# pcb_telemetria.net
KiCad netlist of a schematic drawn in EAGLE
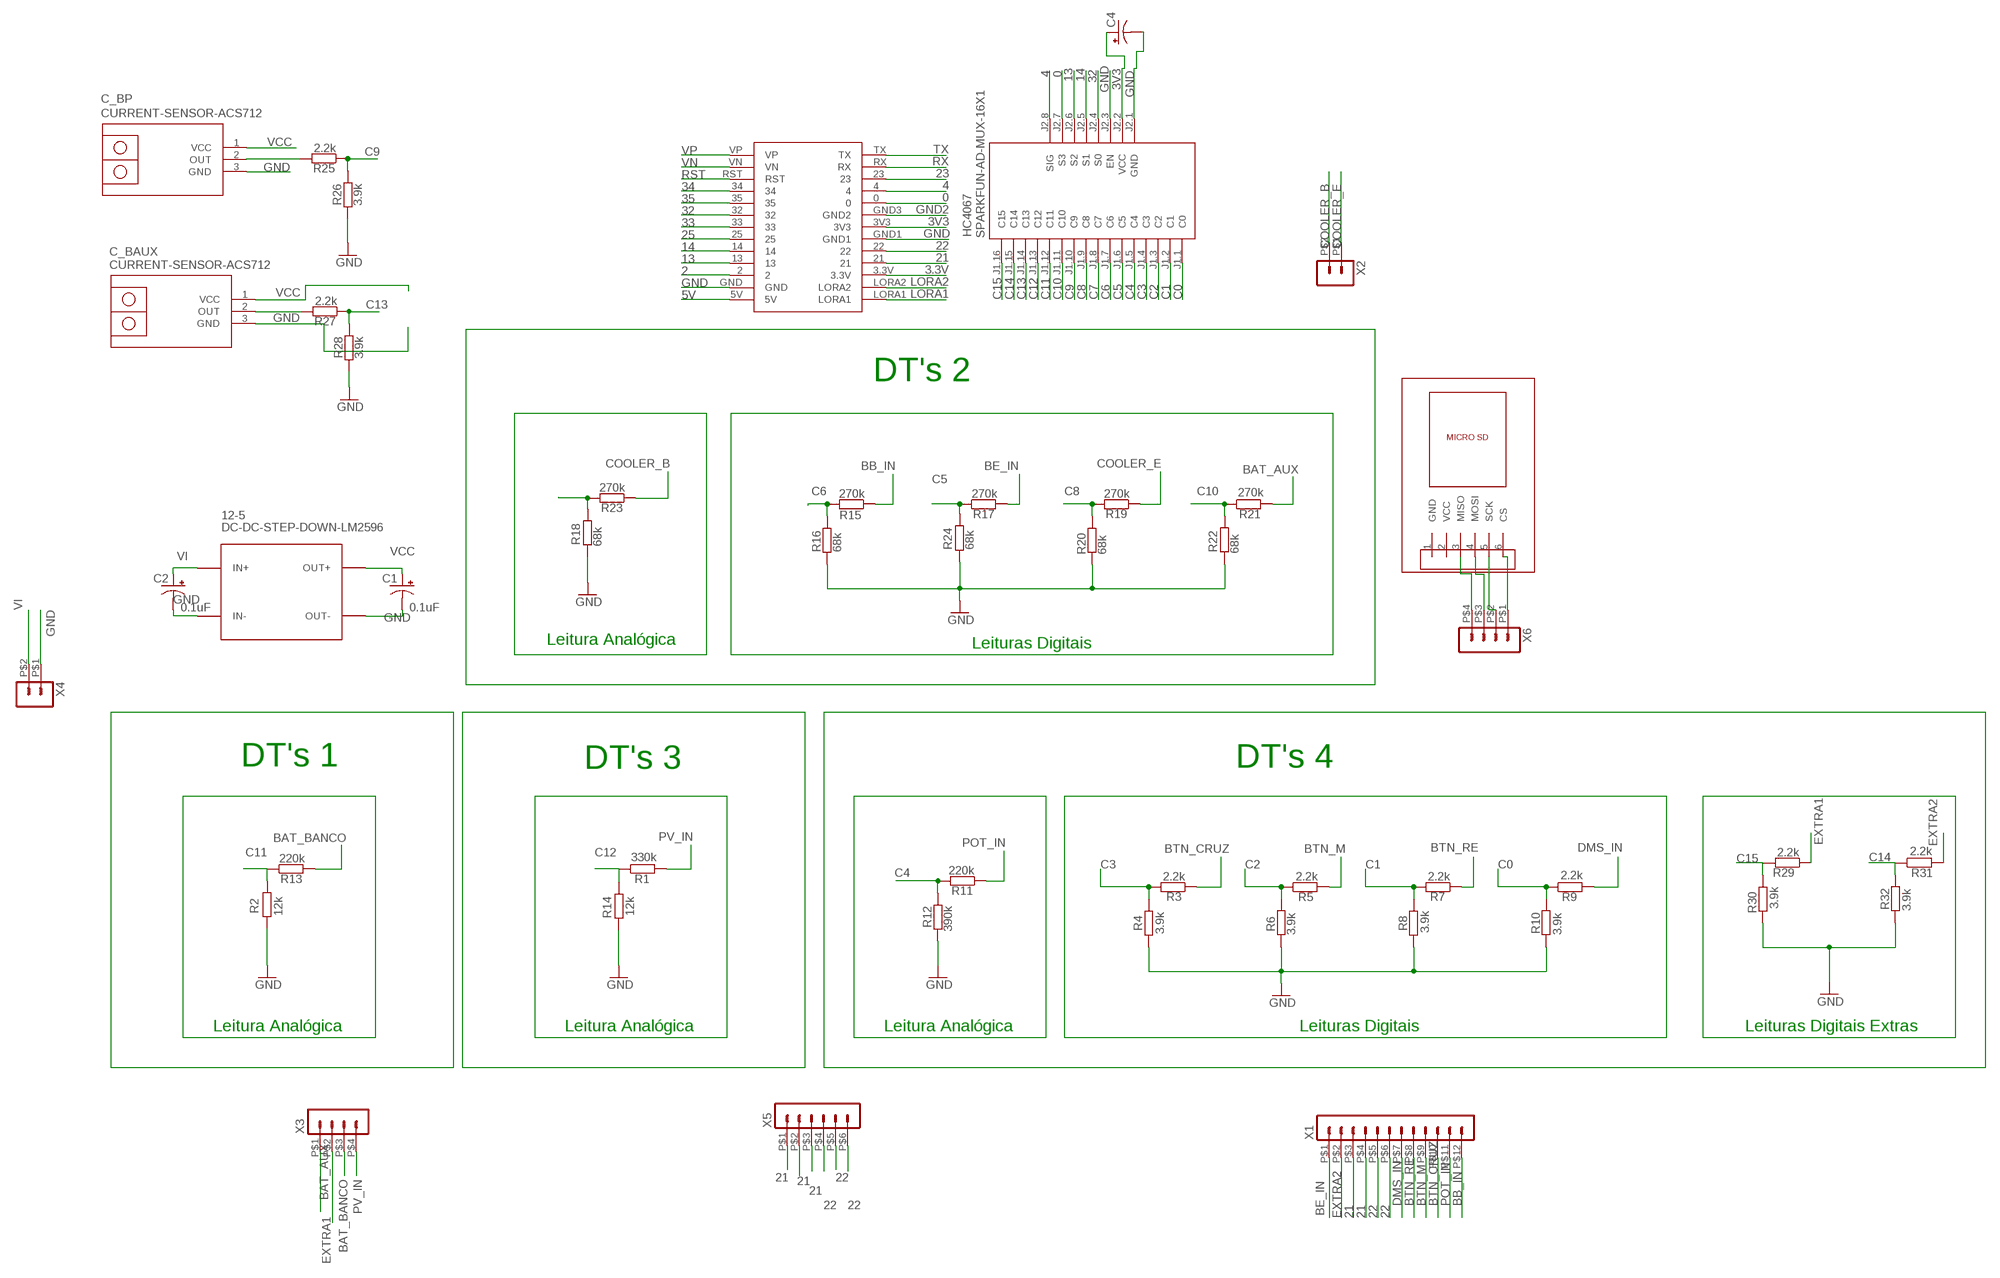
[diagram p0: schematic, sheet 1]

(export (version "E")
  (design (tool "Eeschema 10.0.6"))
  (components
    (comp (ref "12-5")
      (value "DC-DC-STEP-DOWN-LM2596")
      (footprint "eagle-import:DC-DC-STEP-DOWN-LM2596")
      (libsource (lib "eagle-import") (part "DC-DC-STEP-DOWN-LM2596"))
    )
    (comp (ref "C1")
      (value "0.1uF")
      (footprint "eagle-import:E5-5")
      (libsource (lib "eagle-import") (part "CPOL-USE5-5"))
    )
    (comp (ref "C2")
      (value "0.1uF")
      (footprint "eagle-import:E5-5")
      (libsource (lib "eagle-import") (part "CPOL-USE5-5"))
    )
    (comp (ref "C4")
      (value "CPOL-USE5-5")
      (footprint "eagle-import:E5-5")
      (libsource (lib "eagle-import") (part "CPOL-USE5-5"))
    )
    (comp (ref "C_BAUX")
      (value "CURRENT-SENSOR-ACS712")
      (footprint "eagle-import:CURRENT-SENSOR-ACS712")
      (libsource (lib "eagle-import") (part "CURRENT-SENSOR-ACS712"))
    )
    (comp (ref "C_BP")
      (value "CURRENT-SENSOR-ACS712")
      (footprint "eagle-import:CURRENT-SENSOR-ACS712")
      (libsource (lib "eagle-import") (part "CURRENT-SENSOR-ACS712"))
    )
    (comp (ref "HC4067")
      (value "SPARKFUN-AD-MUX-16X1")
      (footprint "eagle-import:SPARKFUN-AD-MUX-16X1")
      (libsource (lib "eagle-import") (part "SPARKFUN-AD-MUX-16X1"))
    )
    (comp (ref "R1")
      (value "330k")
      (footprint "eagle-import:0204_7")
      (libsource (lib "eagle-import") (part "R-EU_0204/7"))
    )
    (comp (ref "R2")
      (value "12k")
      (footprint "eagle-import:0204_7")
      (libsource (lib "eagle-import") (part "R-EU_0204/7"))
    )
    (comp (ref "R3")
      (value "2.2k")
      (footprint "eagle-import:0204_7")
      (libsource (lib "eagle-import") (part "R-EU_0204/7"))
    )
    (comp (ref "R4")
      (value "3.9k")
      (footprint "eagle-import:0204_7")
      (libsource (lib "eagle-import") (part "R-EU_0204/7"))
    )
    (comp (ref "R5")
      (value "2.2k")
      (footprint "eagle-import:0204_7")
      (libsource (lib "eagle-import") (part "R-EU_0204/7"))
    )
    (comp (ref "R6")
      (value "3.9k")
      (footprint "eagle-import:0204_7")
      (libsource (lib "eagle-import") (part "R-EU_0204/7"))
    )
    (comp (ref "R7")
      (value "2.2k")
      (footprint "eagle-import:0204_7")
      (libsource (lib "eagle-import") (part "R-EU_0204/7"))
    )
    (comp (ref "R8")
      (value "3.9k")
      (footprint "eagle-import:0204_7")
      (libsource (lib "eagle-import") (part "R-EU_0204/7"))
    )
    (comp (ref "R9")
      (value "2.2k")
      (footprint "eagle-import:0204_7")
      (libsource (lib "eagle-import") (part "R-EU_0204/7"))
    )
    (comp (ref "R10")
      (value "3.9k")
      (footprint "eagle-import:0204_7")
      (libsource (lib "eagle-import") (part "R-EU_0204/7"))
    )
    (comp (ref "R11")
      (value "220k")
      (footprint "eagle-import:0204_7")
      (libsource (lib "eagle-import") (part "R-EU_0204/7"))
    )
    (comp (ref "R12")
      (value "390k")
      (footprint "eagle-import:0204_7")
      (libsource (lib "eagle-import") (part "R-EU_0204/7"))
    )
    (comp (ref "R13")
      (value "220k")
      (footprint "eagle-import:0204_7")
      (libsource (lib "eagle-import") (part "R-EU_0204/7"))
    )
    (comp (ref "R14")
      (value "12k")
      (footprint "eagle-import:0204_7")
      (libsource (lib "eagle-import") (part "R-EU_0204/7"))
    )
    (comp (ref "R15")
      (value "270k")
      (footprint "eagle-import:0204_7")
      (libsource (lib "eagle-import") (part "R-EU_0204/7"))
    )
    (comp (ref "R16")
      (value "68k")
      (footprint "eagle-import:0204_7")
      (libsource (lib "eagle-import") (part "R-EU_0204/7"))
    )
    (comp (ref "R17")
      (value "270k")
      (footprint "eagle-import:0204_7")
      (libsource (lib "eagle-import") (part "R-EU_0204/7"))
    )
    (comp (ref "R18")
      (value "68k")
      (footprint "eagle-import:0204_7")
      (libsource (lib "eagle-import") (part "R-EU_0204/7"))
    )
    (comp (ref "R19")
      (value "270k")
      (footprint "eagle-import:0204_7")
      (libsource (lib "eagle-import") (part "R-EU_0204/7"))
    )
    (comp (ref "R20")
      (value "68k")
      (footprint "eagle-import:0204_7")
      (libsource (lib "eagle-import") (part "R-EU_0204/7"))
    )
    (comp (ref "R21")
      (value "270k")
      (footprint "eagle-import:0204_7")
      (libsource (lib "eagle-import") (part "R-EU_0204/7"))
    )
    (comp (ref "R22")
      (value "68k")
      (footprint "eagle-import:0204_7")
      (libsource (lib "eagle-import") (part "R-EU_0204/7"))
    )
    (comp (ref "R23")
      (value "270k")
      (footprint "eagle-import:0204_7")
      (libsource (lib "eagle-import") (part "R-EU_0204/7"))
    )
    (comp (ref "R24")
      (value "68k")
      (footprint "eagle-import:0204_7")
      (libsource (lib "eagle-import") (part "R-EU_0204/7"))
    )
    (comp (ref "R25")
      (value "2.2k")
      (footprint "eagle-import:0204_7")
      (libsource (lib "eagle-import") (part "R-EU_0204/7"))
    )
    (comp (ref "R26")
      (value "3.9k")
      (footprint "eagle-import:0204_7")
      (libsource (lib "eagle-import") (part "R-EU_0204/7"))
    )
    (comp (ref "R27")
      (value "2.2k")
      (footprint "eagle-import:0204_7")
      (libsource (lib "eagle-import") (part "R-EU_0204/7"))
    )
    (comp (ref "R28")
      (value "3.9k")
      (footprint "eagle-import:0204_7")
      (libsource (lib "eagle-import") (part "R-EU_0204/7"))
    )
    (comp (ref "R29")
      (value "2.2k")
      (footprint "eagle-import:0204_7")
      (libsource (lib "eagle-import") (part "R-EU_0204/7"))
    )
    (comp (ref "R30")
      (value "3.9k")
      (footprint "eagle-import:0204_7")
      (libsource (lib "eagle-import") (part "R-EU_0204/7"))
    )
    (comp (ref "R31")
      (value "2.2k")
      (footprint "eagle-import:0204_7")
      (libsource (lib "eagle-import") (part "R-EU_0204/7"))
    )
    (comp (ref "R32")
      (value "3.9k")
      (footprint "eagle-import:0204_7")
      (libsource (lib "eagle-import") (part "R-EU_0204/7"))
    )
    (comp (ref "U$1")
      (value "TTGOBEAM")
      (footprint "eagle-import:TTGOBEAM")
      (libsource (lib "eagle-import") (part "TTGOBEAM"))
    )
    (comp (ref "U$2")
      (value "MICRO_SD_MODULE")
      (footprint "eagle-import:MICRO_SD")
      (libsource (lib "eagle-import") (part "MICRO_SD_MODULE"))
    )
    (comp (ref "X1")
      (value "HEADER_POS12_43045-1212")
      (footprint "eagle-import:43045-1212")
      (libsource (lib "eagle-import") (part "HEADER_POS12_?43045-1212"))
    )
    (comp (ref "X2")
      (value "HEADER_POS2_43045-0212")
      (footprint "eagle-import:43045-0212")
      (libsource (lib "eagle-import") (part "HEADER_POS2_?43045-0212"))
    )
    (comp (ref "X3")
      (value "HEADER_POS4_43045-0412")
      (footprint "eagle-import:43045-0412")
      (libsource (lib "eagle-import") (part "HEADER_POS4_?43045-0412"))
    )
    (comp (ref "X4")
      (value "HEADER_POS2_43045-0212")
      (footprint "eagle-import:43045-0212")
      (libsource (lib "eagle-import") (part "HEADER_POS2_?43045-0212"))
    )
    (comp (ref "X5")
      (value "HEADER_POS6_43045-0612")
      (footprint "eagle-import:43045-0612")
      (libsource (lib "eagle-import") (part "HEADER_POS6_?43045-0612"))
    )
    (comp (ref "X6")
      (value "HEADER_POS4_43045-0412")
      (footprint "eagle-import:43045-0412")
      (libsource (lib "eagle-import") (part "HEADER_POS4_?43045-0412"))
    )
  )
  (nets
    (net (code "1") (name "/0") (class "Default")
      (node (ref "HC4067") (pin "J2.7") (pinfunction "S3_J2.7") (pintype "bidirectional"))
      (node (ref "U$1") (pin "0") (pinfunction "0_0") (pintype "bidirectional"))
    )
    (net (code "2") (name "/2") (class "Default")
      (node (ref "U$1") (pin "2") (pinfunction "2_2") (pintype "bidirectional"))
    )
    (net (code "3") (name "/3.3V") (class "Default")
      (node (ref "U$1") (pin "3.3V") (pinfunction "3.3V_3.3V") (pintype "bidirectional"))
    )
    (net (code "4") (name "/3V3") (class "Default")
      (node (ref "C4") (pin "+") (pinfunction "+_+") (pintype "passive"))
      (node (ref "HC4067") (pin "J2.2") (pinfunction "VCC_J2.2") (pintype "power_in"))
      (node (ref "U$1") (pin "3V3") (pinfunction "3V3_3V3") (pintype "bidirectional"))
    )
    (net (code "5") (name "/4") (class "Default")
      (node (ref "HC4067") (pin "J2.8") (pinfunction "SIG_J2.8") (pintype "bidirectional"))
      (node (ref "U$1") (pin "4") (pinfunction "4_4") (pintype "bidirectional"))
    )
    (net (code "6") (name "/5V") (class "Default")
      (node (ref "U$1") (pin "5V") (pinfunction "5V_5V") (pintype "bidirectional"))
    )
    (net (code "7") (name "/13") (class "Default")
      (node (ref "HC4067") (pin "J2.6") (pinfunction "S2_J2.6") (pintype "bidirectional"))
      (node (ref "U$1") (pin "13") (pinfunction "13_13") (pintype "bidirectional"))
    )
    (net (code "8") (name "/14") (class "Default")
      (node (ref "HC4067") (pin "J2.5") (pinfunction "S1_J2.5") (pintype "bidirectional"))
      (node (ref "U$1") (pin "14") (pinfunction "14_14") (pintype "bidirectional"))
    )
    (net (code "9") (name "/21") (class "Default")
      (node (ref "U$1") (pin "21") (pinfunction "21_21") (pintype "bidirectional"))
      (node (ref "X1") (pin "P$3") (pinfunction "3_P$3") (pintype "passive"))
      (node (ref "X1") (pin "P$4") (pinfunction "4_P$4") (pintype "passive"))
      (node (ref "X5") (pin "P$1") (pinfunction "1_P$1") (pintype "passive"))
      (node (ref "X5") (pin "P$2") (pinfunction "2_P$2") (pintype "passive"))
      (node (ref "X5") (pin "P$3") (pinfunction "3_P$3") (pintype "passive"))
    )
    (net (code "10") (name "/22") (class "Default")
      (node (ref "U$1") (pin "22") (pinfunction "22_22") (pintype "bidirectional"))
      (node (ref "X1") (pin "P$5") (pinfunction "5_P$5") (pintype "passive"))
      (node (ref "X1") (pin "P$6") (pinfunction "6_P$6") (pintype "passive"))
      (node (ref "X5") (pin "P$4") (pinfunction "4_P$4") (pintype "passive"))
      (node (ref "X5") (pin "P$5") (pinfunction "5_P$5") (pintype "passive"))
      (node (ref "X5") (pin "P$6") (pinfunction "6_P$6") (pintype "passive"))
    )
    (net (code "11") (name "/23") (class "Default")
      (node (ref "U$1") (pin "23") (pinfunction "23_23") (pintype "bidirectional"))
    )
    (net (code "12") (name "/25") (class "Default")
      (node (ref "U$1") (pin "25") (pinfunction "25_25") (pintype "bidirectional"))
    )
    (net (code "13") (name "/32") (class "Default")
      (node (ref "HC4067") (pin "J2.4") (pinfunction "S0_J2.4") (pintype "bidirectional"))
      (node (ref "U$1") (pin "32") (pinfunction "32_32") (pintype "bidirectional"))
    )
    (net (code "14") (name "/33") (class "Default")
      (node (ref "U$1") (pin "33") (pinfunction "33_33") (pintype "bidirectional"))
    )
    (net (code "15") (name "/34") (class "Default")
      (node (ref "U$1") (pin "34") (pinfunction "34_34") (pintype "bidirectional"))
    )
    (net (code "16") (name "/35") (class "Default")
      (node (ref "U$1") (pin "35") (pinfunction "35_35") (pintype "bidirectional"))
    )
    (net (code "17") (name "/BAT_AUX") (class "Default")
      (node (ref "R21") (pin "2") (pinfunction "2_2") (pintype "passive"))
      (node (ref "X3") (pin "P$1") (pinfunction "1_P$1") (pintype "passive"))
    )
    (net (code "18") (name "/BAT_BANCO") (class "Default")
      (node (ref "R13") (pin "2") (pinfunction "2_2") (pintype "passive"))
      (node (ref "X3") (pin "P$3") (pinfunction "3_P$3") (pintype "passive"))
    )
    (net (code "19") (name "/BB_IN") (class "Default")
      (node (ref "R15") (pin "1") (pinfunction "1_1") (pintype "passive"))
      (node (ref "X1") (pin "P$12") (pinfunction "12_P$12") (pintype "passive"))
    )
    (net (code "20") (name "/BE_IN") (class "Default")
      (node (ref "R17") (pin "2") (pinfunction "2_2") (pintype "passive"))
      (node (ref "X1") (pin "P$1") (pinfunction "1_P$1") (pintype "passive"))
    )
    (net (code "21") (name "/BTN_CRUZ") (class "Default")
      (node (ref "R3") (pin "1") (pinfunction "1_1") (pintype "passive"))
      (node (ref "X1") (pin "P$10") (pinfunction "10_P$10") (pintype "passive"))
    )
    (net (code "22") (name "/BTN_M") (class "Default")
      (node (ref "R5") (pin "2") (pinfunction "2_2") (pintype "passive"))
      (node (ref "X1") (pin "P$9") (pinfunction "9_P$9") (pintype "passive"))
    )
    (net (code "23") (name "/BTN_RE") (class "Default")
      (node (ref "R7") (pin "1") (pinfunction "1_1") (pintype "passive"))
      (node (ref "X1") (pin "P$8") (pinfunction "8_P$8") (pintype "passive"))
    )
    (net (code "24") (name "/C0") (class "Default")
      (node (ref "HC4067") (pin "J1.1") (pinfunction "C0_J1.1") (pintype "bidirectional"))
      (node (ref "R10") (pin "2") (pinfunction "2_2") (pintype "passive"))
      (node (ref "R9") (pin "1") (pinfunction "1_1") (pintype "passive"))
    )
    (net (code "25") (name "/C1") (class "Default")
      (node (ref "HC4067") (pin "J1.2") (pinfunction "C1_J1.2") (pintype "bidirectional"))
      (node (ref "R7") (pin "2") (pinfunction "2_2") (pintype "passive"))
      (node (ref "R8") (pin "1") (pinfunction "1_1") (pintype "passive"))
    )
    (net (code "26") (name "/C2") (class "Default")
      (node (ref "HC4067") (pin "J1.3") (pinfunction "C2_J1.3") (pintype "bidirectional"))
      (node (ref "R5") (pin "1") (pinfunction "1_1") (pintype "passive"))
      (node (ref "R6") (pin "2") (pinfunction "2_2") (pintype "passive"))
    )
    (net (code "27") (name "/C3") (class "Default")
      (node (ref "HC4067") (pin "J1.4") (pinfunction "C3_J1.4") (pintype "bidirectional"))
      (node (ref "R3") (pin "2") (pinfunction "2_2") (pintype "passive"))
      (node (ref "R4") (pin "1") (pinfunction "1_1") (pintype "passive"))
    )
    (net (code "28") (name "/C4") (class "Default")
      (node (ref "HC4067") (pin "J1.5") (pinfunction "C4_J1.5") (pintype "bidirectional"))
      (node (ref "R11") (pin "2") (pinfunction "2_2") (pintype "passive"))
      (node (ref "R12") (pin "1") (pinfunction "1_1") (pintype "passive"))
    )
    (net (code "29") (name "/C5") (class "Default")
      (node (ref "HC4067") (pin "J1.6") (pinfunction "C5_J1.6") (pintype "bidirectional"))
      (node (ref "R17") (pin "1") (pinfunction "1_1") (pintype "passive"))
      (node (ref "R24") (pin "1") (pinfunction "1_1") (pintype "passive"))
    )
    (net (code "30") (name "/C6") (class "Default")
      (node (ref "HC4067") (pin "J1.7") (pinfunction "C6_J1.7") (pintype "bidirectional"))
      (node (ref "R15") (pin "2") (pinfunction "2_2") (pintype "passive"))
      (node (ref "R16") (pin "1") (pinfunction "1_1") (pintype "passive"))
    )
    (net (code "31") (name "/C7") (class "Default")
      (node (ref "HC4067") (pin "J1.8") (pinfunction "C7_J1.8") (pintype "bidirectional"))
      (node (ref "R18") (pin "2") (pinfunction "2_2") (pintype "passive"))
      (node (ref "R23") (pin "2") (pinfunction "2_2") (pintype "passive"))
    )
    (net (code "32") (name "/C8") (class "Default")
      (node (ref "HC4067") (pin "J1.9") (pinfunction "C8_J1.9") (pintype "bidirectional"))
      (node (ref "R19") (pin "2") (pinfunction "2_2") (pintype "passive"))
      (node (ref "R20") (pin "1") (pinfunction "1_1") (pintype "passive"))
    )
    (net (code "33") (name "/C9") (class "Default")
      (node (ref "HC4067") (pin "J1.10") (pinfunction "C9_J1.10") (pintype "bidirectional"))
      (node (ref "R25") (pin "1") (pinfunction "1_1") (pintype "passive"))
      (node (ref "R26") (pin "1") (pinfunction "1_1") (pintype "passive"))
    )
    (net (code "34") (name "/C10") (class "Default")
      (node (ref "HC4067") (pin "J1.11") (pinfunction "C10_J1.11") (pintype "bidirectional"))
      (node (ref "R21") (pin "1") (pinfunction "1_1") (pintype "passive"))
      (node (ref "R22") (pin "2") (pinfunction "2_2") (pintype "passive"))
    )
    (net (code "35") (name "/C11") (class "Default")
      (node (ref "HC4067") (pin "J1.12") (pinfunction "C11_J1.12") (pintype "bidirectional"))
      (node (ref "R13") (pin "1") (pinfunction "1_1") (pintype "passive"))
      (node (ref "R2") (pin "2") (pinfunction "2_2") (pintype "passive"))
    )
    (net (code "36") (name "/C12") (class "Default")
      (node (ref "HC4067") (pin "J1.13") (pinfunction "C12_J1.13") (pintype "bidirectional"))
      (node (ref "R1") (pin "1") (pinfunction "1_1") (pintype "passive"))
      (node (ref "R14") (pin "2") (pinfunction "2_2") (pintype "passive"))
    )
    (net (code "37") (name "/C13") (class "Default")
      (node (ref "HC4067") (pin "J1.14") (pinfunction "C13_J1.14") (pintype "bidirectional"))
      (node (ref "R27") (pin "1") (pinfunction "1_1") (pintype "passive"))
      (node (ref "R28") (pin "1") (pinfunction "1_1") (pintype "passive"))
    )
    (net (code "38") (name "/C14") (class "Default")
      (node (ref "HC4067") (pin "J1.15") (pinfunction "C14_J1.15") (pintype "bidirectional"))
      (node (ref "R31") (pin "1") (pinfunction "1_1") (pintype "passive"))
      (node (ref "R32") (pin "2") (pinfunction "2_2") (pintype "passive"))
    )
    (net (code "39") (name "/C15") (class "Default")
      (node (ref "HC4067") (pin "J1.16") (pinfunction "C15_J1.16") (pintype "bidirectional"))
      (node (ref "R29") (pin "2") (pinfunction "2_2") (pintype "passive"))
      (node (ref "R30") (pin "1") (pinfunction "1_1") (pintype "passive"))
    )
    (net (code "40") (name "/COOLER_B") (class "Default")
      (node (ref "R23") (pin "1") (pinfunction "1_1") (pintype "passive"))
      (node (ref "X2") (pin "P$2") (pinfunction "2_P$2") (pintype "passive"))
    )
    (net (code "41") (name "/COOLER_E") (class "Default")
      (node (ref "R19") (pin "1") (pinfunction "1_1") (pintype "passive"))
      (node (ref "X2") (pin "P$1") (pinfunction "1_P$1") (pintype "passive"))
    )
    (net (code "42") (name "/DMS_IN") (class "Default")
      (node (ref "R9") (pin "2") (pinfunction "2_2") (pintype "passive"))
      (node (ref "X1") (pin "P$7") (pinfunction "7_P$7") (pintype "passive"))
    )
    (net (code "43") (name "/EXTRA1") (class "Default")
      (node (ref "R29") (pin "1") (pinfunction "1_1") (pintype "passive"))
      (node (ref "X3") (pin "P$2") (pinfunction "2_P$2") (pintype "passive"))
    )
    (net (code "44") (name "/EXTRA2") (class "Default")
      (node (ref "R31") (pin "2") (pinfunction "2_2") (pintype "passive"))
      (node (ref "X1") (pin "P$2") (pinfunction "2_P$2") (pintype "passive"))
    )
    (net (code "45") (name "/GND2") (class "Default")
      (node (ref "U$1") (pin "GND3") (pinfunction "GND2_GND3") (pintype "bidirectional"))
    )
    (net (code "46") (name "/LORA1") (class "Default")
      (node (ref "U$1") (pin "LORA1") (pinfunction "LORA1_LORA1") (pintype "bidirectional"))
    )
    (net (code "47") (name "/LORA2") (class "Default")
      (node (ref "U$1") (pin "LORA2") (pinfunction "LORA2_LORA2") (pintype "bidirectional"))
    )
    (net (code "48") (name "/POT_IN") (class "Default")
      (node (ref "R11") (pin "1") (pinfunction "1_1") (pintype "passive"))
      (node (ref "X1") (pin "P$11") (pinfunction "11_P$11") (pintype "passive"))
    )
    (net (code "49") (name "/PV_IN") (class "Default")
      (node (ref "R1") (pin "2") (pinfunction "2_2") (pintype "passive"))
      (node (ref "X3") (pin "P$4") (pinfunction "4_P$4") (pintype "passive"))
    )
    (net (code "50") (name "/RST") (class "Default")
      (node (ref "U$1") (pin "RST") (pinfunction "RST_RST") (pintype "bidirectional"))
    )
    (net (code "51") (name "/RX") (class "Default")
      (node (ref "U$1") (pin "RX") (pinfunction "RX_RX") (pintype "bidirectional"))
    )
    (net (code "52") (name "/TX") (class "Default")
      (node (ref "U$1") (pin "TX") (pinfunction "TX_TX") (pintype "bidirectional"))
    )
    (net (code "53") (name "/VCC") (class "Default")
      (node (ref "12-5") (pin "OUT+") (pinfunction "OUT+_OUT+") (pintype "bidirectional"))
      (node (ref "C1") (pin "+") (pinfunction "+_+") (pintype "passive"))
      (node (ref "C_BAUX") (pin "1") (pinfunction "VCC_1") (pintype "power_in"))
      (node (ref "C_BP") (pin "1") (pinfunction "VCC_1") (pintype "power_in"))
    )
    (net (code "54") (name "/VI") (class "Default")
      (node (ref "12-5") (pin "IN+") (pinfunction "IN+_IN+") (pintype "bidirectional"))
      (node (ref "C2") (pin "+") (pinfunction "+_+") (pintype "passive"))
      (node (ref "X4") (pin "P$2") (pinfunction "2_P$2") (pintype "passive"))
    )
    (net (code "55") (name "/VN") (class "Default")
      (node (ref "U$1") (pin "VN") (pinfunction "VN_VN") (pintype "bidirectional"))
    )
    (net (code "56") (name "/VP") (class "Default")
      (node (ref "U$1") (pin "VP") (pinfunction "VP_VP") (pintype "bidirectional"))
    )
    (net (code "57") (name "GND") (class "Default")
      (node (ref "12-5") (pin "IN-") (pinfunction "IN-_IN-") (pintype "bidirectional"))
      (node (ref "12-5") (pin "OUT-") (pinfunction "OUT-_OUT-") (pintype "bidirectional"))
      (node (ref "C1") (pin "-") (pinfunction "-_-") (pintype "passive"))
      (node (ref "C2") (pin "-") (pinfunction "-_-") (pintype "passive"))
      (node (ref "C4") (pin "-") (pinfunction "-_-") (pintype "passive"))
      (node (ref "C_BAUX") (pin "3") (pinfunction "GND_3") (pintype "power_in"))
      (node (ref "C_BP") (pin "3") (pinfunction "GND_3") (pintype "power_in"))
      (node (ref "HC4067") (pin "J2.1") (pinfunction "GND_J2.1") (pintype "power_in"))
      (node (ref "HC4067") (pin "J2.3") (pinfunction "EN_J2.3") (pintype "input"))
      (node (ref "R10") (pin "1") (pinfunction "1_1") (pintype "passive"))
      (node (ref "R12") (pin "2") (pinfunction "2_2") (pintype "passive"))
      (node (ref "R14") (pin "1") (pinfunction "1_1") (pintype "passive"))
      (node (ref "R16") (pin "2") (pinfunction "2_2") (pintype "passive"))
      (node (ref "R18") (pin "1") (pinfunction "1_1") (pintype "passive"))
      (node (ref "R2") (pin "1") (pinfunction "1_1") (pintype "passive"))
      (node (ref "R20") (pin "2") (pinfunction "2_2") (pintype "passive"))
      (node (ref "R22") (pin "1") (pinfunction "1_1") (pintype "passive"))
      (node (ref "R26") (pin "2") (pinfunction "2_2") (pintype "passive"))
      (node (ref "R28") (pin "2") (pinfunction "2_2") (pintype "passive"))
      (node (ref "R30") (pin "2") (pinfunction "2_2") (pintype "passive"))
      (node (ref "R32") (pin "1") (pinfunction "1_1") (pintype "passive"))
      (node (ref "R4") (pin "2") (pinfunction "2_2") (pintype "passive"))
      (node (ref "R6") (pin "1") (pinfunction "1_1") (pintype "passive"))
      (node (ref "R8") (pin "2") (pinfunction "2_2") (pintype "passive"))
      (node (ref "U$1") (pin "GND") (pinfunction "GND_GND") (pintype "bidirectional"))
      (node (ref "U$1") (pin "GND1") (pinfunction "GND1_GND1") (pintype "bidirectional"))
      (node (ref "X4") (pin "P$1") (pinfunction "1_P$1") (pintype "passive"))
    )
    (net (code "58") (name "Net-(C_BAUX-OUT)") (class "Default")
      (node (ref "C_BAUX") (pin "2") (pinfunction "OUT_2") (pintype "output"))
      (node (ref "R27") (pin "2") (pinfunction "2_2") (pintype "passive"))
    )
    (net (code "59") (name "Net-(C_BP-OUT)") (class "Default")
      (node (ref "C_BP") (pin "2") (pinfunction "OUT_2") (pintype "output"))
      (node (ref "R25") (pin "2") (pinfunction "2_2") (pintype "passive"))
    )
    (net (code "60") (name "Net-(U$2-CS)") (class "Default")
      (node (ref "U$2") (pin "6") (pinfunction "CS_6") (pintype "input"))
      (node (ref "X6") (pin "P$1") (pinfunction "1_P$1") (pintype "passive"))
    )
    (net (code "61") (name "Net-(U$2-MISO)") (class "Default")
      (node (ref "U$2") (pin "3") (pinfunction "MISO_3") (pintype "bidirectional"))
      (node (ref "X6") (pin "P$4") (pinfunction "4_P$4") (pintype "passive"))
    )
    (net (code "62") (name "Net-(U$2-MOSI)") (class "Default")
      (node (ref "U$2") (pin "4") (pinfunction "MOSI_4") (pintype "bidirectional"))
      (node (ref "X6") (pin "P$3") (pinfunction "3_P$3") (pintype "passive"))
    )
    (net (code "63") (name "Net-(U$2-SCK)") (class "Default")
      (node (ref "U$2") (pin "5") (pinfunction "SCK_5") (pintype "input"))
      (node (ref "X6") (pin "P$2") (pinfunction "2_P$2") (pintype "passive"))
    )
    (net (code "64") (name "unconnected-(R24-Pad2)") (class "Default")
      (node (ref "R24") (pin "2") (pinfunction "2_2") (pintype "passive"))
    )
    (net (code "65") (name "unconnected-(U$2-GND-Pad1)") (class "Default")
      (node (ref "U$2") (pin "1") (pinfunction "GND_1") (pintype "bidirectional"))
    )
    (net (code "66") (name "unconnected-(U$2-VCC-Pad2)") (class "Default")
      (node (ref "U$2") (pin "2") (pinfunction "VCC_2") (pintype "bidirectional"))
    )
  )
)
